# MCU.net
KiCad netlist of a schematic drawn in Altium Designer
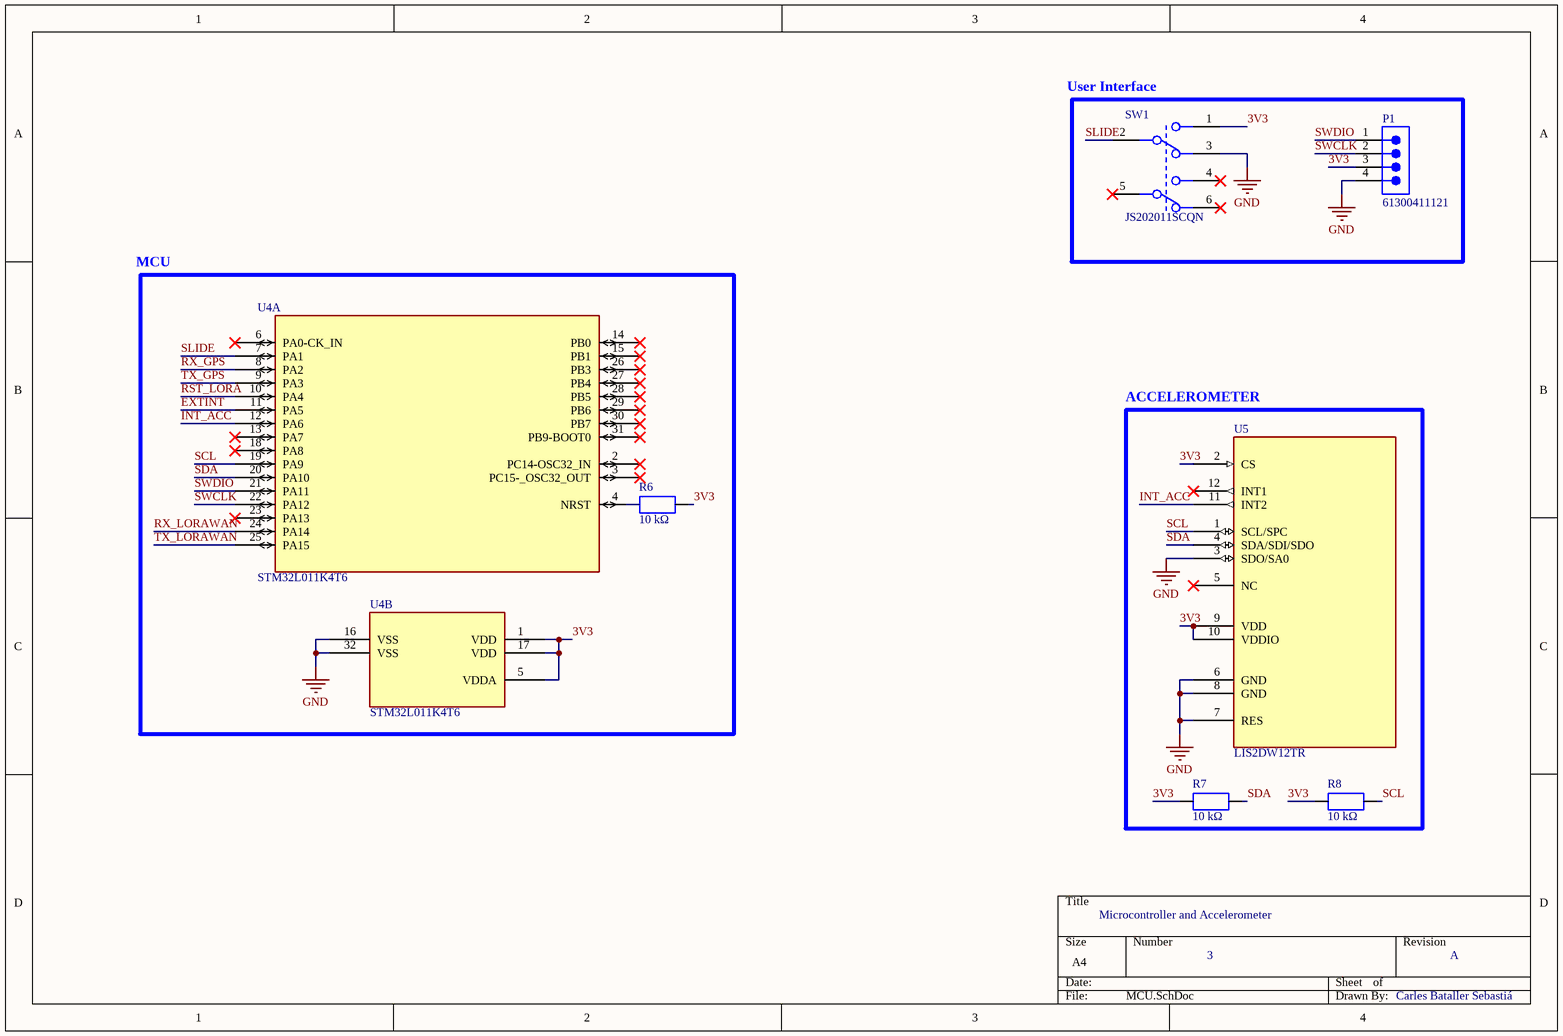
[diagram p0: MCU.SchDoc]

(export (version "E")
  (design (tool "Eeschema 10.0.6"))
  (components
    (comp (ref "P1")
      (value "61300411121")
      (footprint "61300411121")
      (description "THT Vertical Pin Header WR-PHD, Pitch 2.54 mm, Single Row, 4 pins")
      (libsource (lib "Generic-Schematic-Library") (part "CMP-1502-01064-4"))
    )
    (comp (ref "R6")
      (value "10 kΩ")
      (footprint "RES_0201")
      (description "Thick Film Resistors - SMD 0201 10K0 1% Lead Free")
      (fields (field (name "TOLERANCE") "0.1%") (field (name "LCSC PART NUMBER") "C852221"))
      (libsource (lib "Generic-Schematic-Library") (part "RES_0201"))
    )
    (comp (ref "R7")
      (value "10 kΩ")
      (footprint "RES_0201")
      (description "Thick Film Resistors - SMD 0201 10K0 1% Lead Free")
      (fields (field (name "TOLERANCE") "0.1%") (field (name "LCSC PART NUMBER") "C852221"))
      (libsource (lib "Generic-Schematic-Library") (part "RES_0201"))
    )
    (comp (ref "R8")
      (value "10 kΩ")
      (footprint "RES_0201")
      (description "Thick Film Resistors - SMD 0201 10K0 1% Lead Free")
      (fields (field (name "TOLERANCE") "0.1%") (field (name "LCSC PART NUMBER") "C852221"))
      (libsource (lib "Generic-Schematic-Library") (part "RES_0201"))
    )
    (comp (ref "SW1")
      (value "JS202011SCQN")
      (footprint "FP-JS202011SCQN-MFG")
      (description "SWITCH SLIDE DPDT 300MA 6V")
      (libsource (lib "Generic-Schematic-Library") (part "CMP-2000-05087-3"))
    )
    (comp (ref "U4")
      (value "STM32L011K4T6")
      (footprint "LQFP32_7X7X1P4")
      (description "Ultra-low-power Arm Cortex-M0+ MCU with 16-Kbytes of Flash memory, 32 MHz CPU")
      (fields (field (name "COPYRIGHT") "Copyright (C) 2026 Ultra Librarian. All rights reserved."))
      (libsource (lib "Generic-Schematic-Library") (part "STM32L011K4T6"))
    )
    (comp (ref "U5")
      (value "LIS2DW12TR")
      (footprint "LGA-12_2X2X0P7_STM")
      (fields (field (name "COPYRIGHT") "Copyright (C) 2026 Ultra Librarian. All rights reserved."))
      (libsource (lib "Generic-Schematic-Library") (part "LIS2DW12TR"))
    )
  )
  (nets
    (net (code "1") (name "/3V3") (class "Default")
      (node (ref "P1") (pin "3") (pinfunction "3_3") (pintype "passive"))
      (node (ref "R6") (pin "1") (pinfunction "1_1") (pintype "passive"))
      (node (ref "R7") (pin "2") (pinfunction "2_2") (pintype "passive"))
      (node (ref "R8") (pin "2") (pinfunction "2_2") (pintype "passive"))
      (node (ref "SW1") (pin "1") (pinfunction "1_1") (pintype "passive"))
      (node (ref "U4") (pin "1") (pinfunction "VDD_1") (pintype "power_in"))
      (node (ref "U4") (pin "17") (pinfunction "VDD_17") (pintype "power_in"))
      (node (ref "U4") (pin "5") (pinfunction "VDDA_5") (pintype "power_in"))
      (node (ref "U5") (pin "10") (pinfunction "VDDIO_10") (pintype "power_in"))
      (node (ref "U5") (pin "2") (pinfunction "CS_2") (pintype "input"))
      (node (ref "U5") (pin "9") (pinfunction "VDD_9") (pintype "power_in"))
    )
    (net (code "2") (name "/EXTINT") (class "Default")
      (node (ref "U4") (pin "11") (pinfunction "PA5_11") (pintype "passive"))
    )
    (net (code "3") (name "/INT_ACC") (class "Default")
      (node (ref "U4") (pin "12") (pinfunction "PA6_12") (pintype "passive"))
      (node (ref "U5") (pin "11") (pinfunction "INT2_11") (pintype "output"))
    )
    (net (code "4") (name "/RST_LORA") (class "Default")
      (node (ref "U4") (pin "10") (pinfunction "PA4_10") (pintype "passive"))
    )
    (net (code "5") (name "/RX_GPS") (class "Default")
      (node (ref "U4") (pin "8") (pinfunction "PA2_8") (pintype "passive"))
    )
    (net (code "6") (name "/RX_LORAWAN") (class "Default")
      (node (ref "U4") (pin "24") (pinfunction "PA14_24") (pintype "passive"))
    )
    (net (code "7") (name "/SCL") (class "Default")
      (node (ref "R8") (pin "1") (pinfunction "1_1") (pintype "passive"))
      (node (ref "U4") (pin "19") (pinfunction "PA9_19") (pintype "passive"))
      (node (ref "U5") (pin "1") (pinfunction "SCL/SPC_1") (pintype "bidirectional"))
    )
    (net (code "8") (name "/SDA") (class "Default")
      (node (ref "R7") (pin "1") (pinfunction "1_1") (pintype "passive"))
      (node (ref "U4") (pin "20") (pinfunction "PA10_20") (pintype "passive"))
      (node (ref "U5") (pin "4") (pinfunction "SDA/SDI/SDO_4") (pintype "bidirectional"))
    )
    (net (code "9") (name "/SLIDE") (class "Default")
      (node (ref "SW1") (pin "2") (pinfunction "2_2") (pintype "passive"))
      (node (ref "U4") (pin "7") (pinfunction "PA1_7") (pintype "passive"))
    )
    (net (code "10") (name "/SWCLK") (class "Default")
      (node (ref "P1") (pin "2") (pinfunction "2_2") (pintype "passive"))
      (node (ref "U4") (pin "22") (pinfunction "PA12_22") (pintype "passive"))
    )
    (net (code "11") (name "/SWDIO") (class "Default")
      (node (ref "P1") (pin "1") (pinfunction "1_1") (pintype "passive"))
      (node (ref "U4") (pin "21") (pinfunction "PA11_21") (pintype "passive"))
    )
    (net (code "12") (name "/TX_GPS") (class "Default")
      (node (ref "U4") (pin "9") (pinfunction "PA3_9") (pintype "passive"))
    )
    (net (code "13") (name "/TX_LORAWAN") (class "Default")
      (node (ref "U4") (pin "25") (pinfunction "PA15_25") (pintype "passive"))
    )
    (net (code "14") (name "GND") (class "Default")
      (node (ref "P1") (pin "4") (pinfunction "4_4") (pintype "passive"))
      (node (ref "SW1") (pin "3") (pinfunction "3_3") (pintype "passive"))
      (node (ref "U4") (pin "16") (pinfunction "VSS_16") (pintype "power_in"))
      (node (ref "U4") (pin "32") (pinfunction "VSS_32") (pintype "power_in"))
      (node (ref "U5") (pin "3") (pinfunction "SDO/SA0_3") (pintype "bidirectional"))
      (node (ref "U5") (pin "6") (pinfunction "GND_6") (pintype "power_in"))
      (node (ref "U5") (pin "7") (pinfunction "RES_7") (pintype "power_in"))
      (node (ref "U5") (pin "8") (pinfunction "GND_8") (pintype "power_in"))
    )
    (net (code "15") (name "Net-(U4A-NRST)") (class "Default")
      (node (ref "R6") (pin "2") (pinfunction "2_2") (pintype "passive"))
      (node (ref "U4") (pin "4") (pinfunction "NRST_4") (pintype "passive"))
    )
    (net (code "16") (name "unconnected-(SW1-Pad4)") (class "Default")
      (node (ref "SW1") (pin "4") (pinfunction "4_4") (pintype "passive+no_connect"))
    )
    (net (code "17") (name "unconnected-(SW1-Pad5)") (class "Default")
      (node (ref "SW1") (pin "5") (pinfunction "5_5") (pintype "passive+no_connect"))
    )
    (net (code "18") (name "unconnected-(SW1-Pad6)") (class "Default")
      (node (ref "SW1") (pin "6") (pinfunction "6_6") (pintype "passive+no_connect"))
    )
    (net (code "19") (name "unconnected-(U4A-PA0-CK_IN-Pad6)") (class "Default")
      (node (ref "U4") (pin "6") (pinfunction "PA0-CK_IN_6") (pintype "passive+no_connect"))
    )
    (net (code "20") (name "unconnected-(U4A-PA7-Pad13)") (class "Default")
      (node (ref "U4") (pin "13") (pinfunction "PA7_13") (pintype "passive+no_connect"))
    )
    (net (code "21") (name "unconnected-(U4A-PA8-Pad18)") (class "Default")
      (node (ref "U4") (pin "18") (pinfunction "PA8_18") (pintype "passive+no_connect"))
    )
    (net (code "22") (name "unconnected-(U4A-PA13-Pad23)") (class "Default")
      (node (ref "U4") (pin "23") (pinfunction "PA13_23") (pintype "passive+no_connect"))
    )
    (net (code "23") (name "unconnected-(U4A-PB0-Pad14)") (class "Default")
      (node (ref "U4") (pin "14") (pinfunction "PB0_14") (pintype "passive+no_connect"))
    )
    (net (code "24") (name "unconnected-(U4A-PB1-Pad15)") (class "Default")
      (node (ref "U4") (pin "15") (pinfunction "PB1_15") (pintype "passive+no_connect"))
    )
    (net (code "25") (name "unconnected-(U4A-PB3-Pad26)") (class "Default")
      (node (ref "U4") (pin "26") (pinfunction "PB3_26") (pintype "passive+no_connect"))
    )
    (net (code "26") (name "unconnected-(U4A-PB4-Pad27)") (class "Default")
      (node (ref "U4") (pin "27") (pinfunction "PB4_27") (pintype "passive+no_connect"))
    )
    (net (code "27") (name "unconnected-(U4A-PB5-Pad28)") (class "Default")
      (node (ref "U4") (pin "28") (pinfunction "PB5_28") (pintype "passive+no_connect"))
    )
    (net (code "28") (name "unconnected-(U4A-PB6-Pad29)") (class "Default")
      (node (ref "U4") (pin "29") (pinfunction "PB6_29") (pintype "passive+no_connect"))
    )
    (net (code "29") (name "unconnected-(U4A-PB7-Pad30)") (class "Default")
      (node (ref "U4") (pin "30") (pinfunction "PB7_30") (pintype "passive+no_connect"))
    )
    (net (code "30") (name "unconnected-(U4A-PB9-BOOT0-Pad31)") (class "Default")
      (node (ref "U4") (pin "31") (pinfunction "PB9-BOOT0_31") (pintype "passive+no_connect"))
    )
    (net (code "31") (name "unconnected-(U4A-PC14-OSC32_IN-Pad2)") (class "Default")
      (node (ref "U4") (pin "2") (pinfunction "PC14-OSC32_IN_2") (pintype "passive+no_connect"))
    )
    (net (code "32") (name "unconnected-(U4A-PC15-_OSC32_OUT-Pad3)") (class "Default")
      (node (ref "U4") (pin "3") (pinfunction "PC15-_OSC32_OUT_3") (pintype "passive+no_connect"))
    )
    (net (code "33") (name "unconnected-(U5-INT1-Pad12)") (class "Default")
      (node (ref "U5") (pin "12") (pinfunction "INT1_12") (pintype "output+no_connect"))
    )
    (net (code "34") (name "unconnected-(U5-NC-Pad5)") (class "Default")
      (node (ref "U5") (pin "5") (pinfunction "NC_5") (pintype "passive+no_connect"))
    )
  )
)
